# RAM.net
KiCad netlist of a schematic drawn in Altium Designer
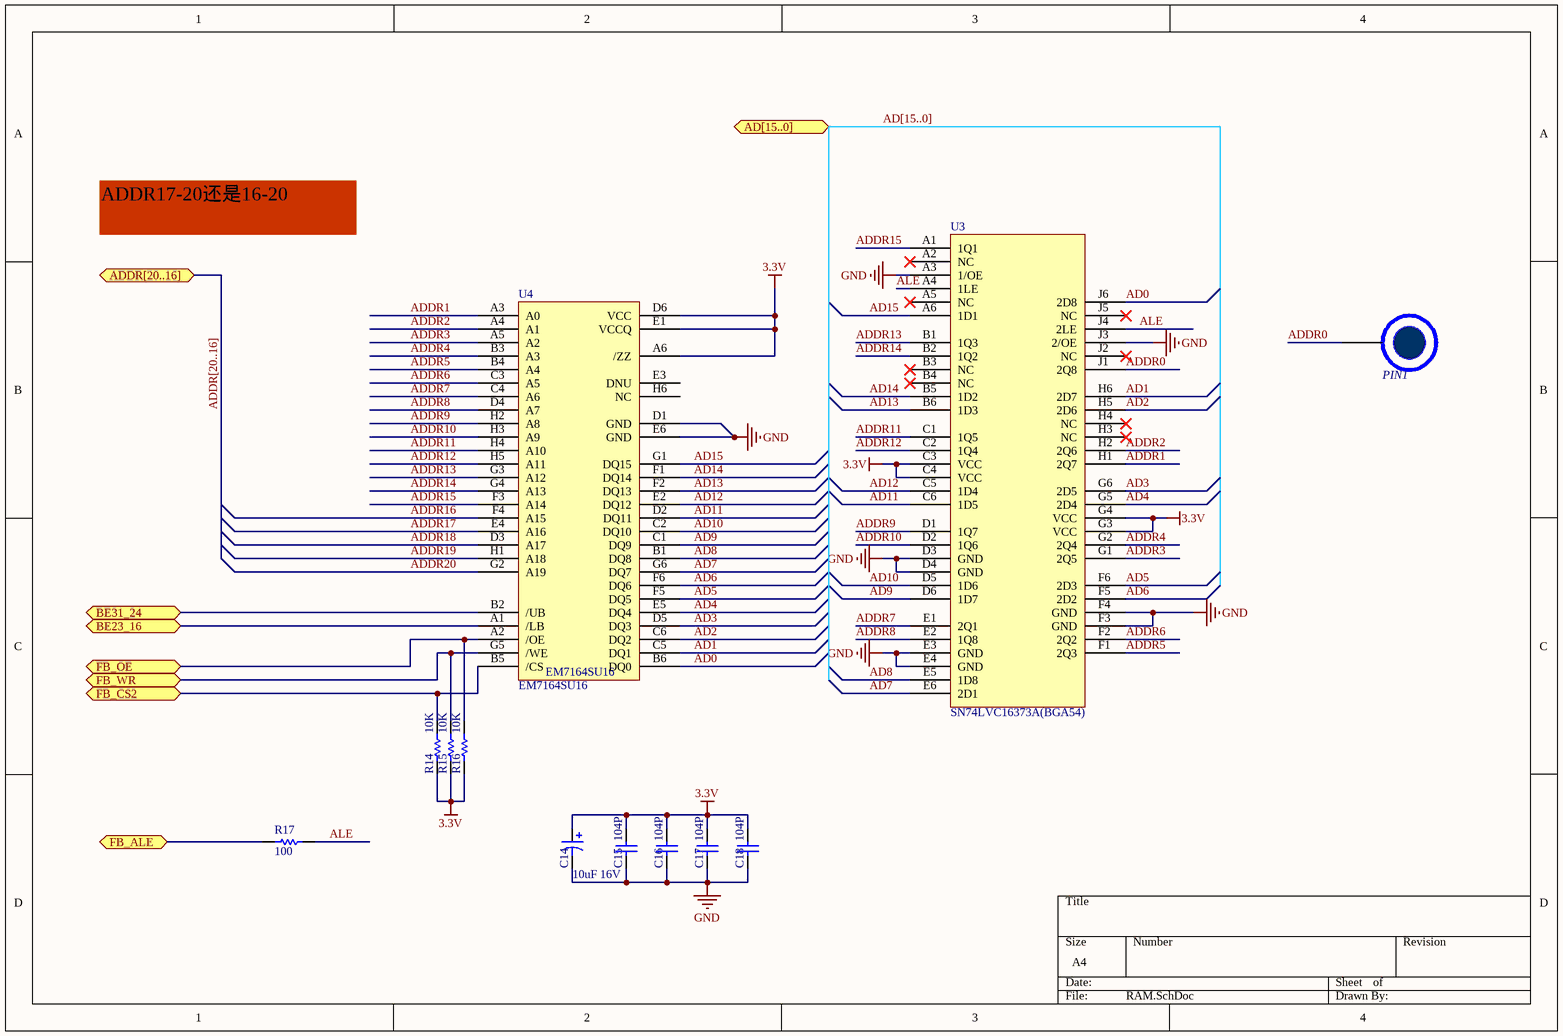
[diagram p0: RAM.SchDoc]

(export (version "E")
  (design (tool "Eeschema 10.0.6"))
  (components
    (comp (ref "C14")
      (value "10uF 16V")
      (footprint "0402")
      (description "Polarized Capacitor (Radial)")
      (fields (field (name "Comment") "Cap Pol1") (field (name "PUBLISHER") "Altium Limited"))
      (libsource (lib "Miscellaneous Devices") (part "Cap Pol1"))
    )
    (comp (ref "C15")
      (value "104P")
      (footprint "0402")
      (description "贴片电容")
      (fields (field (name "Comment") "Cap") (field (name "PUBLISHER") "Altium Limited"))
      (libsource (lib "Sparks") (part "Cap"))
    )
    (comp (ref "C16")
      (value "104P")
      (footprint "0402")
      (description "贴片电容")
      (fields (field (name "Comment") "Cap") (field (name "PUBLISHER") "Altium Limited"))
      (libsource (lib "Sparks") (part "Cap"))
    )
    (comp (ref "C17")
      (value "104P")
      (footprint "0402")
      (description "贴片电容")
      (fields (field (name "Comment") "Cap") (field (name "PUBLISHER") "Altium Limited"))
      (libsource (lib "Sparks") (part "Cap"))
    )
    (comp (ref "C18")
      (value "104P")
      (footprint "0402")
      (description "贴片电容")
      (fields (field (name "Comment") "Cap") (field (name "PUBLISHER") "Altium Limited"))
      (libsource (lib "Sparks") (part "Cap"))
    )
    (comp (ref "PIN1") (value "PIN") (footprint "PIN") (libsource (lib "2号库") (part "PIN")))
    (comp (ref "R14")
      (value "10K")
      (footprint "0402")
      (description "贴片电阻")
      (fields (field (name "Comment") "Res") (field (name "PUBLISHER") "Altium Limited"))
      (libsource (lib "Sparks") (part "Res"))
    )
    (comp (ref "R15")
      (value "10K")
      (footprint "0402")
      (description "贴片电阻")
      (fields (field (name "Comment") "Res") (field (name "PUBLISHER") "Altium Limited"))
      (libsource (lib "Sparks") (part "Res"))
    )
    (comp (ref "R16")
      (value "10K")
      (footprint "0402")
      (description "贴片电阻")
      (fields (field (name "Comment") "Res") (field (name "PUBLISHER") "Altium Limited"))
      (libsource (lib "Sparks") (part "Res"))
    )
    (comp (ref "R17")
      (value "100")
      (footprint "0402")
      (description "贴片电阻")
      (fields (field (name "Comment") "Res") (field (name "PUBLISHER") "Altium Limited"))
      (libsource (lib "Sparks") (part "Res"))
    )
    (comp (ref "U3")
      (value "SN74LVC16373A(BGA54)")
      (footprint "BGA54C80P6X9_550X800X120")
      (libsource (lib "2号库") (part "SN74LVC16373A(BGA54)"))
    )
    (comp (ref "U4")
      (value "EM7164SU16")
      (footprint "BGA48C75P6X8_598X698X104")
      (libsource (lib "2号库") (part "EM7164SU16"))
    )
  )
  (nets
    (net (code "1") (name "/AD0") (class "Default")
      (node (ref "U3") (pin "J6") (pinfunction "2D8_J6") (pintype "passive"))
      (node (ref "U4") (pin "B6") (pinfunction "DQ0_B6") (pintype "passive"))
    )
    (net (code "2") (name "/AD1") (class "Default")
      (node (ref "U3") (pin "H6") (pinfunction "2D7_H6") (pintype "passive"))
      (node (ref "U4") (pin "C5") (pinfunction "DQ1_C5") (pintype "passive"))
    )
    (net (code "3") (name "/AD2") (class "Default")
      (node (ref "U3") (pin "H5") (pinfunction "2D6_H5") (pintype "passive"))
      (node (ref "U4") (pin "C6") (pinfunction "DQ2_C6") (pintype "passive"))
    )
    (net (code "4") (name "/AD3") (class "Default")
      (node (ref "U3") (pin "G6") (pinfunction "2D5_G6") (pintype "passive"))
      (node (ref "U4") (pin "D5") (pinfunction "DQ3_D5") (pintype "passive"))
    )
    (net (code "5") (name "/AD4") (class "Default")
      (node (ref "U3") (pin "G5") (pinfunction "2D4_G5") (pintype "passive"))
      (node (ref "U4") (pin "E5") (pinfunction "DQ4_E5") (pintype "passive"))
    )
    (net (code "6") (name "/AD5") (class "Default")
      (node (ref "U3") (pin "F6") (pinfunction "2D3_F6") (pintype "passive"))
      (node (ref "U4") (pin "F5") (pinfunction "DQ5_F5") (pintype "passive"))
    )
    (net (code "7") (name "/AD6") (class "Default")
      (node (ref "U3") (pin "F5") (pinfunction "2D2_F5") (pintype "passive"))
      (node (ref "U4") (pin "F6") (pinfunction "DQ6_F6") (pintype "passive"))
    )
    (net (code "8") (name "/AD7") (class "Default")
      (node (ref "U3") (pin "E6") (pinfunction "2D1_E6") (pintype "passive"))
      (node (ref "U4") (pin "G6") (pinfunction "DQ7_G6") (pintype "passive"))
    )
    (net (code "9") (name "/AD8") (class "Default")
      (node (ref "U3") (pin "E5") (pinfunction "1D8_E5") (pintype "passive"))
      (node (ref "U4") (pin "B1") (pinfunction "DQ8_B1") (pintype "passive"))
    )
    (net (code "10") (name "/AD9") (class "Default")
      (node (ref "U3") (pin "D6") (pinfunction "1D7_D6") (pintype "passive"))
      (node (ref "U4") (pin "C1") (pinfunction "DQ9_C1") (pintype "passive"))
    )
    (net (code "11") (name "/AD10") (class "Default")
      (node (ref "U3") (pin "D5") (pinfunction "1D6_D5") (pintype "passive"))
      (node (ref "U4") (pin "C2") (pinfunction "DQ10_C2") (pintype "passive"))
    )
    (net (code "12") (name "/AD11") (class "Default")
      (node (ref "U3") (pin "C6") (pinfunction "1D5_C6") (pintype "passive"))
      (node (ref "U4") (pin "D2") (pinfunction "DQ11_D2") (pintype "passive"))
    )
    (net (code "13") (name "/AD12") (class "Default")
      (node (ref "U3") (pin "C5") (pinfunction "1D4_C5") (pintype "passive"))
      (node (ref "U4") (pin "E2") (pinfunction "DQ12_E2") (pintype "passive"))
    )
    (net (code "14") (name "/AD13") (class "Default")
      (node (ref "U3") (pin "B6") (pinfunction "1D3_B6") (pintype "passive"))
      (node (ref "U4") (pin "F2") (pinfunction "DQ13_F2") (pintype "passive"))
    )
    (net (code "15") (name "/AD14") (class "Default")
      (node (ref "U3") (pin "B5") (pinfunction "1D2_B5") (pintype "passive"))
      (node (ref "U4") (pin "F1") (pinfunction "DQ14_F1") (pintype "passive"))
    )
    (net (code "16") (name "/AD15") (class "Default")
      (node (ref "U3") (pin "A6") (pinfunction "1D1_A6") (pintype "passive"))
      (node (ref "U4") (pin "G1") (pinfunction "DQ15_G1") (pintype "passive"))
    )
    (net (code "17") (name "/ADDR0") (class "Default")
      (node (ref "PIN1") (pin "1") (pinfunction "PIN_1") (pintype "passive"))
      (node (ref "U3") (pin "J1") (pinfunction "2Q8_J1") (pintype "passive"))
    )
    (net (code "18") (name "/ADDR1") (class "Default")
      (node (ref "U3") (pin "H1") (pinfunction "2Q7_H1") (pintype "passive"))
      (node (ref "U4") (pin "A3") (pinfunction "A0_A3") (pintype "passive"))
    )
    (net (code "19") (name "/ADDR2") (class "Default")
      (node (ref "U3") (pin "H2") (pinfunction "2Q6_H2") (pintype "passive"))
      (node (ref "U4") (pin "A4") (pinfunction "A1_A4") (pintype "passive"))
    )
    (net (code "20") (name "/ADDR3") (class "Default")
      (node (ref "U3") (pin "G1") (pinfunction "2Q5_G1") (pintype "passive"))
      (node (ref "U4") (pin "A5") (pinfunction "A2_A5") (pintype "passive"))
    )
    (net (code "21") (name "/ADDR4") (class "Default")
      (node (ref "U3") (pin "G2") (pinfunction "2Q4_G2") (pintype "passive"))
      (node (ref "U4") (pin "B3") (pinfunction "A3_B3") (pintype "passive"))
    )
    (net (code "22") (name "/ADDR5") (class "Default")
      (node (ref "U3") (pin "F1") (pinfunction "2Q3_F1") (pintype "passive"))
      (node (ref "U4") (pin "B4") (pinfunction "A4_B4") (pintype "passive"))
    )
    (net (code "23") (name "/ADDR6") (class "Default")
      (node (ref "U3") (pin "F2") (pinfunction "2Q2_F2") (pintype "passive"))
      (node (ref "U4") (pin "C3") (pinfunction "A5_C3") (pintype "passive"))
    )
    (net (code "24") (name "/ADDR7") (class "Default")
      (node (ref "U3") (pin "E1") (pinfunction "2Q1_E1") (pintype "passive"))
      (node (ref "U4") (pin "C4") (pinfunction "A6_C4") (pintype "passive"))
    )
    (net (code "25") (name "/ADDR8") (class "Default")
      (node (ref "U3") (pin "E2") (pinfunction "1Q8_E2") (pintype "passive"))
      (node (ref "U4") (pin "D4") (pinfunction "A7_D4") (pintype "passive"))
    )
    (net (code "26") (name "/ADDR9") (class "Default")
      (node (ref "U3") (pin "D1") (pinfunction "1Q7_D1") (pintype "passive"))
      (node (ref "U4") (pin "H2") (pinfunction "A8_H2") (pintype "passive"))
    )
    (net (code "27") (name "/ADDR10") (class "Default")
      (node (ref "U3") (pin "D2") (pinfunction "1Q6_D2") (pintype "passive"))
      (node (ref "U4") (pin "H3") (pinfunction "A9_H3") (pintype "passive"))
    )
    (net (code "28") (name "/ADDR11") (class "Default")
      (node (ref "U3") (pin "C1") (pinfunction "1Q5_C1") (pintype "passive"))
      (node (ref "U4") (pin "H4") (pinfunction "A10_H4") (pintype "passive"))
    )
    (net (code "29") (name "/ADDR12") (class "Default")
      (node (ref "U3") (pin "C2") (pinfunction "1Q4_C2") (pintype "passive"))
      (node (ref "U4") (pin "H5") (pinfunction "A11_H5") (pintype "passive"))
    )
    (net (code "30") (name "/ADDR13") (class "Default")
      (node (ref "U3") (pin "B1") (pinfunction "1Q3_B1") (pintype "passive"))
      (node (ref "U4") (pin "G3") (pinfunction "A12_G3") (pintype "passive"))
    )
    (net (code "31") (name "/ADDR14") (class "Default")
      (node (ref "U3") (pin "B2") (pinfunction "1Q2_B2") (pintype "passive"))
      (node (ref "U4") (pin "G4") (pinfunction "A13_G4") (pintype "passive"))
    )
    (net (code "32") (name "/ADDR15") (class "Default")
      (node (ref "U3") (pin "A1") (pinfunction "1Q1_A1") (pintype "passive"))
      (node (ref "U4") (pin "F3") (pinfunction "A14_F3") (pintype "passive"))
    )
    (net (code "33") (name "/ADDR16") (class "Default")
      (node (ref "U4") (pin "F4") (pinfunction "A15_F4") (pintype "passive"))
    )
    (net (code "34") (name "/ADDR17") (class "Default")
      (node (ref "U4") (pin "E4") (pinfunction "A16_E4") (pintype "passive"))
    )
    (net (code "35") (name "/ADDR18") (class "Default")
      (node (ref "U4") (pin "D3") (pinfunction "A17_D3") (pintype "passive"))
    )
    (net (code "36") (name "/ADDR19") (class "Default")
      (node (ref "U4") (pin "H1") (pinfunction "A18_H1") (pintype "passive"))
    )
    (net (code "37") (name "/ADDR20") (class "Default")
      (node (ref "U4") (pin "G2") (pinfunction "A19_G2") (pintype "passive"))
    )
    (net (code "40") (name "/ALE") (class "Default")
      (node (ref "R17") (pin "2") (pinfunction "2_2") (pintype "passive"))
      (node (ref "U3") (pin "A4") (pinfunction "1LE_A4") (pintype "passive"))
      (node (ref "U3") (pin "J4") (pinfunction "2LE_J4") (pintype "passive"))
    )
    (net (code "41") (name "/BE23_16") (class "Default")
      (node (ref "U4") (pin "A1") (pinfunction "/LB_A1") (pintype "passive"))
    )
    (net (code "42") (name "/BE31_24") (class "Default")
      (node (ref "U4") (pin "B2") (pinfunction "/UB_B2") (pintype "passive"))
    )
    (net (code "43") (name "/FB_ALE") (class "Default")
      (node (ref "R17") (pin "1") (pinfunction "1_1") (pintype "passive"))
    )
    (net (code "44") (name "/FB_CS2") (class "Default")
      (node (ref "R14") (pin "1") (pinfunction "1_1") (pintype "passive"))
      (node (ref "U4") (pin "B5") (pinfunction "/CS_B5") (pintype "passive"))
    )
    (net (code "45") (name "/FB_OE") (class "Default")
      (node (ref "R16") (pin "1") (pinfunction "1_1") (pintype "passive"))
      (node (ref "U4") (pin "A2") (pinfunction "/OE_A2") (pintype "passive"))
    )
    (net (code "46") (name "/FB_WR") (class "Default")
      (node (ref "R15") (pin "1") (pinfunction "1_1") (pintype "passive"))
      (node (ref "U4") (pin "G5") (pinfunction "/WE_G5") (pintype "passive"))
    )
    (net (code "47") (name "3.3V") (class "Default")
      (node (ref "C14") (pin "1") (pinfunction "1_1") (pintype "passive"))
      (node (ref "C15") (pin "2") (pinfunction "2_2") (pintype "passive"))
      (node (ref "C16") (pin "2") (pinfunction "2_2") (pintype "passive"))
      (node (ref "C17") (pin "2") (pinfunction "2_2") (pintype "passive"))
      (node (ref "C18") (pin "2") (pinfunction "2_2") (pintype "passive"))
      (node (ref "R14") (pin "2") (pinfunction "2_2") (pintype "passive"))
      (node (ref "R15") (pin "2") (pinfunction "2_2") (pintype "passive"))
      (node (ref "R16") (pin "2") (pinfunction "2_2") (pintype "passive"))
      (node (ref "U3") (pin "C3") (pinfunction "VCC_C3") (pintype "passive"))
      (node (ref "U3") (pin "C4") (pinfunction "VCC_C4") (pintype "passive"))
      (node (ref "U3") (pin "G3") (pinfunction "VCC_G3") (pintype "passive"))
      (node (ref "U3") (pin "G4") (pinfunction "VCC_G4") (pintype "passive"))
      (node (ref "U4") (pin "A6") (pinfunction "/ZZ_A6") (pintype "passive"))
      (node (ref "U4") (pin "D6") (pinfunction "VCC_D6") (pintype "passive"))
      (node (ref "U4") (pin "E1") (pinfunction "VCCQ_E1") (pintype "passive"))
    )
    (net (code "48") (name "GND") (class "Default")
      (node (ref "C14") (pin "2") (pinfunction "2_2") (pintype "passive"))
      (node (ref "C15") (pin "1") (pinfunction "1_1") (pintype "passive"))
      (node (ref "C16") (pin "1") (pinfunction "1_1") (pintype "passive"))
      (node (ref "C17") (pin "1") (pinfunction "1_1") (pintype "passive"))
      (node (ref "C18") (pin "1") (pinfunction "1_1") (pintype "passive"))
      (node (ref "U3") (pin "A3") (pinfunction "1/OE_A3") (pintype "passive"))
      (node (ref "U3") (pin "D3") (pinfunction "GND_D3") (pintype "passive"))
      (node (ref "U3") (pin "D4") (pinfunction "GND_D4") (pintype "passive"))
      (node (ref "U3") (pin "E3") (pinfunction "GND_E3") (pintype "passive"))
      (node (ref "U3") (pin "E4") (pinfunction "GND_E4") (pintype "passive"))
      (node (ref "U3") (pin "F3") (pinfunction "GND_F3") (pintype "passive"))
      (node (ref "U3") (pin "F4") (pinfunction "GND_F4") (pintype "passive"))
      (node (ref "U3") (pin "J3") (pinfunction "2/OE_J3") (pintype "passive"))
      (node (ref "U4") (pin "D1") (pinfunction "GND_D1") (pintype "passive"))
      (node (ref "U4") (pin "E6") (pinfunction "GND_E6") (pintype "passive"))
    )
    (net (code "49") (name "unconnected-(U3-NC-PadA2)") (class "Default")
      (node (ref "U3") (pin "A2") (pinfunction "NC_A2") (pintype "passive+no_connect"))
    )
    (net (code "50") (name "unconnected-(U3-NC-PadA5)") (class "Default")
      (node (ref "U3") (pin "A5") (pinfunction "NC_A5") (pintype "passive+no_connect"))
    )
    (net (code "51") (name "unconnected-(U3-NC-PadB3)") (class "Default")
      (node (ref "U3") (pin "B3") (pinfunction "NC_B3") (pintype "passive+no_connect"))
    )
    (net (code "52") (name "unconnected-(U3-NC-PadB4)") (class "Default")
      (node (ref "U3") (pin "B4") (pinfunction "NC_B4") (pintype "passive+no_connect"))
    )
    (net (code "53") (name "unconnected-(U3-NC-PadH3)") (class "Default")
      (node (ref "U3") (pin "H3") (pinfunction "NC_H3") (pintype "passive+no_connect"))
    )
    (net (code "54") (name "unconnected-(U3-NC-PadH4)") (class "Default")
      (node (ref "U3") (pin "H4") (pinfunction "NC_H4") (pintype "passive+no_connect"))
    )
    (net (code "55") (name "unconnected-(U3-NC-PadJ2)") (class "Default")
      (node (ref "U3") (pin "J2") (pinfunction "NC_J2") (pintype "passive+no_connect"))
    )
    (net (code "56") (name "unconnected-(U3-NC-PadJ5)") (class "Default")
      (node (ref "U3") (pin "J5") (pinfunction "NC_J5") (pintype "passive+no_connect"))
    )
    (net (code "57") (name "unconnected-(U4-DNU-PadE3)") (class "Default")
      (node (ref "U4") (pin "E3") (pinfunction "DNU_E3") (pintype "passive"))
    )
    (net (code "58") (name "unconnected-(U4-NC-PadH6)") (class "Default")
      (node (ref "U4") (pin "H6") (pinfunction "NC_H6") (pintype "passive"))
    )
  )
)
